# USB.net
KiCad netlist of a schematic drawn in Altium Designer
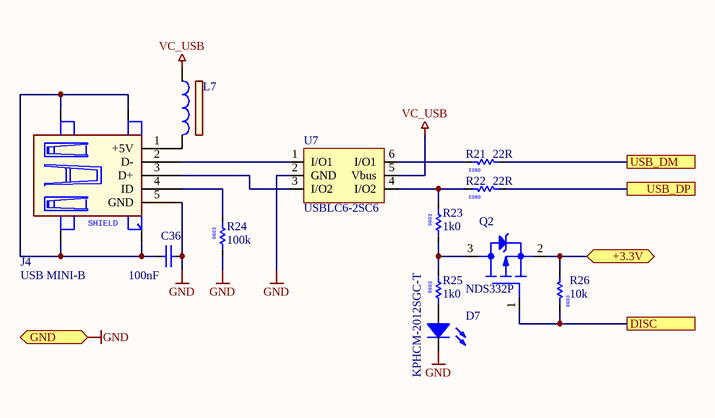
[diagram p0: USB.SchDoc]

(export (version "E")
  (design (tool "Eeschema 10.0.6"))
  (components
    (comp (ref "C36")
      (value "100nF")
      (footprint "C0603V")
      (description "MLCC, 0.1uF 16V 10% X7R 0603")
      (fields (field (name "PART NUMBER") "C0000005") (field (name "VOLTAGE") "16"))
      (libsource (lib "KTU_DB") (part "C_SM"))
    )
    (comp (ref "D7")
      (value "KPHCM-2012SGC-T")
      (footprint "D0805")
      (description "LED, SMD, 0805, GREEN, 25mcd")
      (fields (field (name "PART NUMBER") "D0000030") (field (name "MANUFACTURER") "KINGBRIGHT"))
      (libsource (lib "KTU_DB") (part "LED"))
    )
    (comp (ref "J4")
      (value "USB MINI-B")
      (footprint "MOLEX_MINI_USB-B")
      (description "USB MINI-B SMT connector")
      (fields (field (name "PART NUMBER") "J0000002") (field (name "MANUFACTURER") "Molex"))
      (libsource (lib "KTU_DB") (part "Mini_USB_B"))
    )
    (comp (ref "L7")
      (value "~")
      (footprint "LL0805\\2P")
      (description "BEAD SMD EMI FERRITE 0805 220 OHM")
      (fields (field (name "PART NUMBER") "L0000002") (field (name "MANUFACTURER") "Murata"))
      (libsource (lib "KTU_DB") (part "L_core"))
    )
    (comp (ref "Q2")
      (value "NDS332P")
      (footprint "SOT23-3L")
      (description "P-Channel Logic Level Enhancement Mode Field Effect Transistor")
      (fields (field (name "PART NUMBER") "Q0000046") (field (name "MANUFACTURER") "FAIRCHILD SEMICONDUCTOR"))
      (libsource (lib "KTU_DB") (part "MOSFET_P_GSD"))
    )
    (comp (ref "R21")
      (value "22R")
      (footprint "RESC1608N")
      (description "Res, 22R 5% 0603 1/10W")
      (fields (field (name "TOLERANCE") "±5%") (field (name "POWER") "1/10W"))
      (libsource (lib "KTU_DB") (part "R0603"))
    )
    (comp (ref "R22")
      (value "22R")
      (footprint "RESC1608N")
      (description "Res, 22R 5% 0603 1/10W")
      (fields (field (name "TOLERANCE") "±5%") (field (name "POWER") "1/10W"))
      (libsource (lib "KTU_DB") (part "R0603"))
    )
    (comp (ref "R23")
      (value "1k0")
      (footprint "RESC1608N")
      (description "Res, thin film 1k  ±5% 0.1W 0603")
      (fields (field (name "TOLERANCE") "±5%") (field (name "POWER") "0.1W"))
      (libsource (lib "KTU_DB") (part "R0603"))
    )
    (comp (ref "R24")
      (value "100k")
      (footprint "RESC1608N")
      (description "Res, 100K 5% 0603 1/10W")
      (fields (field (name "TOLERANCE") "±1%") (field (name "POWER") "1/10W"))
      (libsource (lib "KTU_DB") (part "R0603"))
    )
    (comp (ref "R25")
      (value "1k0")
      (footprint "RESC1608N")
      (description "Res, thin film 1k  ±5% 0.1W 0603")
      (fields (field (name "TOLERANCE") "±5%") (field (name "POWER") "0.1W"))
      (libsource (lib "KTU_DB") (part "R0603"))
    )
    (comp (ref "R26")
      (value "10k")
      (footprint "RESC1608N")
      (description "Res, 10K 0.063W 75V 1%  0603")
      (fields (field (name "TOLERANCE") "±1%") (field (name "POWER") "0.063W"))
      (libsource (lib "KTU_DB") (part "R0603"))
    )
    (comp (ref "U7")
      (value "USBLC6-2SC6")
      (footprint "SOT95P280X145-6N")
      (description "DIODE ARRAY, TVS, USB2")
      (fields (field (name "MANUFACTURER") "STMICROELECTRONICS") (field (name "PART NUMBER") "D0000115"))
      (libsource (lib "KTU_DB") (part "USBLC6-2"))
    )
  )
  (nets
    (net (code "1") (name "/+3.3V") (class "Default")
      (node (ref "Q2") (pin "2") (pinfunction "S_2") (pintype "passive"))
      (node (ref "R26") (pin "2") (pinfunction "2_2") (pintype "passive"))
    )
    (net (code "2") (name "/DISC") (class "Default")
      (node (ref "Q2") (pin "1") (pinfunction "G_1") (pintype "passive"))
      (node (ref "R26") (pin "1") (pinfunction "1_1") (pintype "passive"))
    )
    (net (code "3") (name "/USB_DM") (class "Default")
      (node (ref "R21") (pin "2") (pinfunction "2_2") (pintype "passive"))
    )
    (net (code "4") (name "/USB_DP") (class "Default")
      (node (ref "R22") (pin "2") (pinfunction "2_2") (pintype "passive"))
    )
    (net (code "5") (name "GND") (class "Default")
      (node (ref "C36") (pin "1") (pinfunction "1_1") (pintype "passive"))
      (node (ref "D7") (pin "2") (pinfunction "2_2") (pintype "passive"))
      (node (ref "J4") (pin "5") (pinfunction "GND_5") (pintype "passive"))
      (node (ref "R24") (pin "1") (pinfunction "1_1") (pintype "passive"))
      (node (ref "U7") (pin "2") (pinfunction "GND_2") (pintype "passive"))
    )
    (net (code "6") (name "Net-(C36-Pad2)") (class "Default")
      (node (ref "C36") (pin "2") (pinfunction "2_2") (pintype "passive"))
      (node (ref "J4") (pin "6") (pinfunction "SHIELD_6") (pintype "passive"))
      (node (ref "J4") (pin "7") (pinfunction "SHIELD_7") (pintype "passive"))
      (node (ref "J4") (pin "8") (pinfunction "SHIELD_8") (pintype "passive"))
      (node (ref "J4") (pin "9") (pinfunction "SHIELD_9") (pintype "passive"))
    )
    (net (code "7") (name "Net-(D7-Pad1)") (class "Default")
      (node (ref "D7") (pin "1") (pinfunction "1_1") (pintype "passive"))
      (node (ref "R25") (pin "1") (pinfunction "1_1") (pintype "passive"))
    )
    (net (code "8") (name "Net-(J4-+5V)") (class "Default")
      (node (ref "J4") (pin "1") (pinfunction "+5V_1") (pintype "passive"))
      (node (ref "L7") (pin "2") (pinfunction "2_2") (pintype "passive"))
    )
    (net (code "9") (name "Net-(J4-D+)") (class "Default")
      (node (ref "J4") (pin "3") (pinfunction "D+_3") (pintype "passive"))
      (node (ref "U7") (pin "3") (pinfunction "I/O2_3") (pintype "bidirectional"))
    )
    (net (code "10") (name "Net-(J4-D-)") (class "Default")
      (node (ref "J4") (pin "2") (pinfunction "D-_2") (pintype "passive"))
      (node (ref "U7") (pin "1") (pinfunction "I/O1_1") (pintype "bidirectional"))
    )
    (net (code "11") (name "Net-(J4-ID)") (class "Default")
      (node (ref "J4") (pin "4") (pinfunction "ID_4") (pintype "passive"))
      (node (ref "R24") (pin "2") (pinfunction "2_2") (pintype "passive"))
    )
    (net (code "12") (name "Net-(Q2-D)") (class "Default")
      (node (ref "Q2") (pin "3") (pinfunction "D_3") (pintype "passive"))
      (node (ref "R23") (pin "1") (pinfunction "1_1") (pintype "passive"))
      (node (ref "R25") (pin "2") (pinfunction "2_2") (pintype "passive"))
    )
    (net (code "13") (name "Net-(R21-Pad1)") (class "Default")
      (node (ref "R21") (pin "1") (pinfunction "1_1") (pintype "passive"))
      (node (ref "U7") (pin "6") (pinfunction "I/O1_6") (pintype "bidirectional"))
    )
    (net (code "14") (name "Net-(R22-Pad1)") (class "Default")
      (node (ref "R22") (pin "1") (pinfunction "1_1") (pintype "passive"))
      (node (ref "R23") (pin "2") (pinfunction "2_2") (pintype "passive"))
      (node (ref "U7") (pin "4") (pinfunction "I/O2_4") (pintype "bidirectional"))
    )
    (net (code "15") (name "VC_USB") (class "Default")
      (node (ref "L7") (pin "1") (pinfunction "1_1") (pintype "passive"))
      (node (ref "U7") (pin "5") (pinfunction "Vbus_5") (pintype "passive"))
    )
  )
)
